# PSU_v1_0.net
KiCad netlist of a schematic drawn in EAGLE
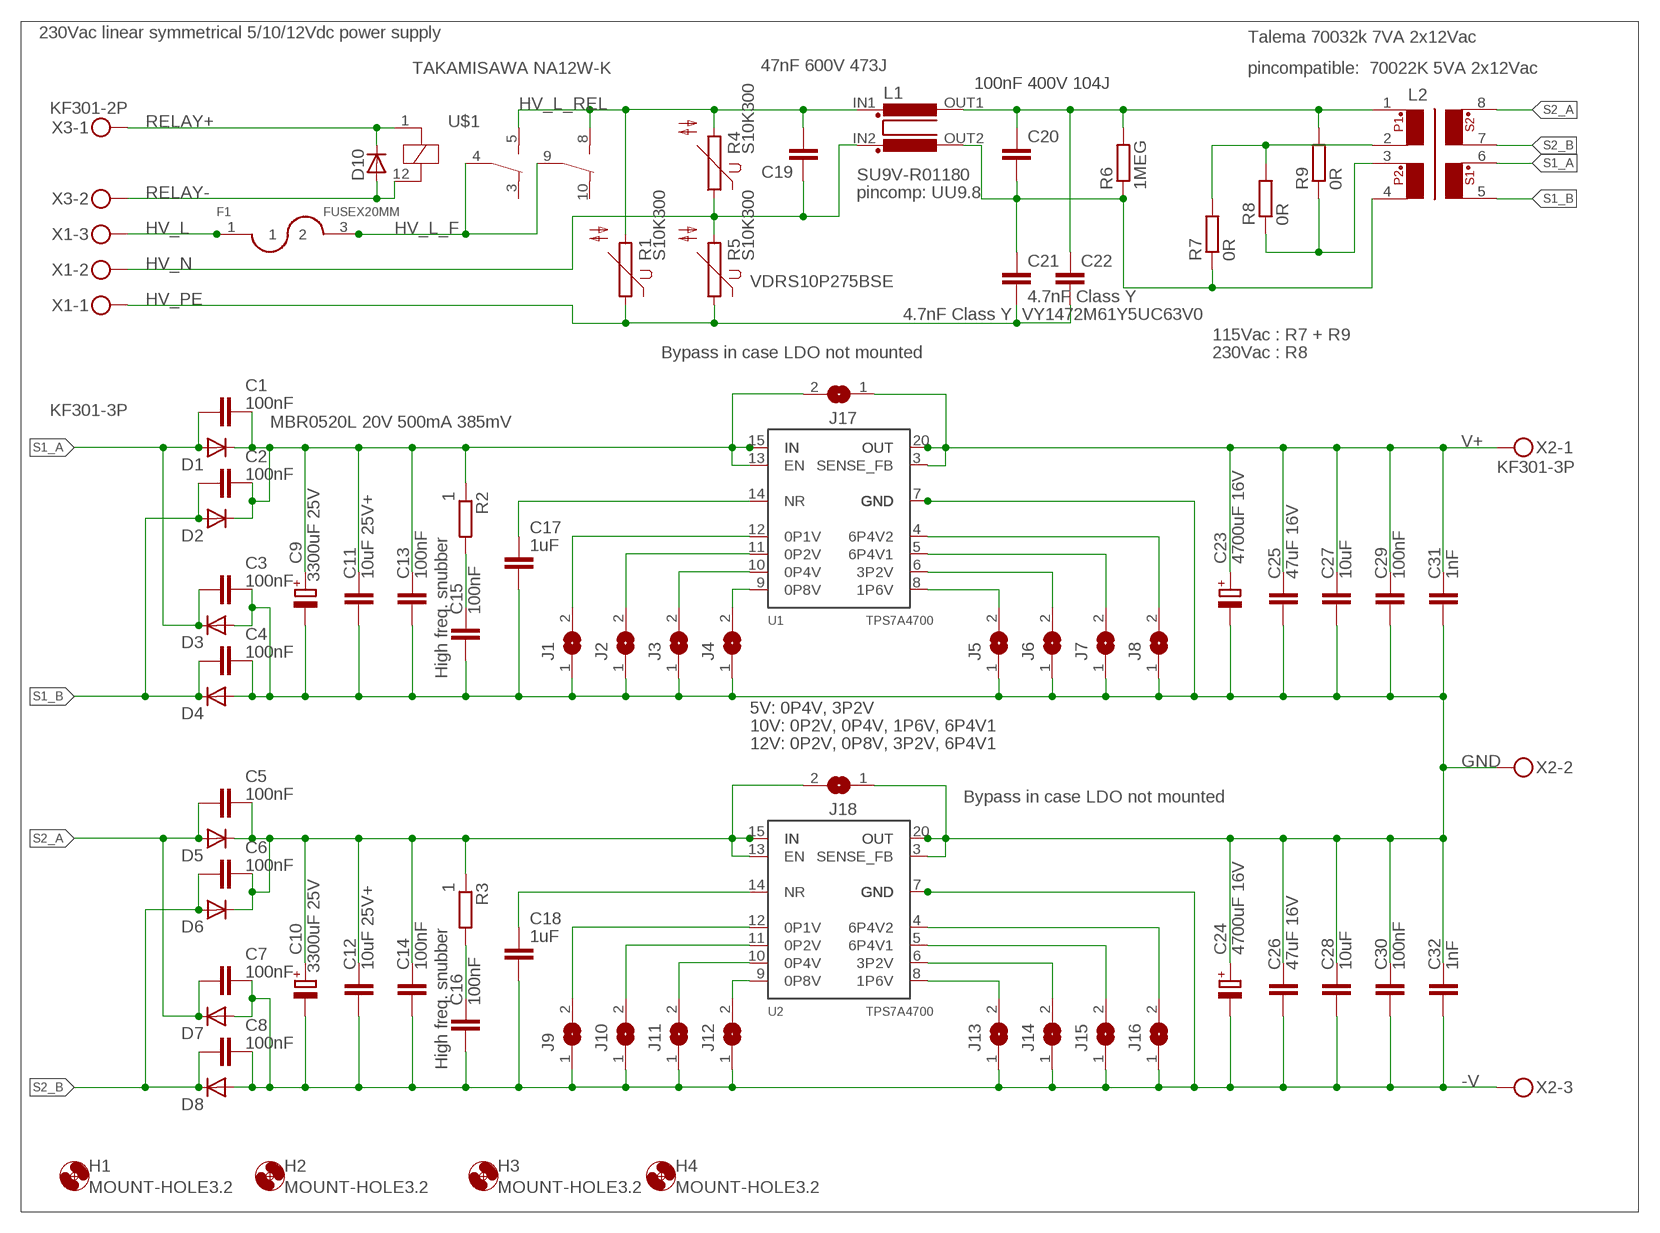
[diagram p0: schematic, sheet 1]

(export (version "E")
  (design (tool "Eeschema 10.0.6"))
  (components
    (comp (ref "C1")
      (value "100nF")
      (footprint "eagle-import:C0603")
      (libsource (lib "eagle-import") (part "C-EUC0603"))
    )
    (comp (ref "C2")
      (value "100nF")
      (footprint "eagle-import:C0603")
      (libsource (lib "eagle-import") (part "C-EUC0603"))
    )
    (comp (ref "C3")
      (value "100nF")
      (footprint "eagle-import:C0603")
      (libsource (lib "eagle-import") (part "C-EUC0603"))
    )
    (comp (ref "C4")
      (value "100nF")
      (footprint "eagle-import:C0603")
      (libsource (lib "eagle-import") (part "C-EUC0603"))
    )
    (comp (ref "C5")
      (value "100nF")
      (footprint "eagle-import:C0603")
      (libsource (lib "eagle-import") (part "C-EUC0603"))
    )
    (comp (ref "C6")
      (value "100nF")
      (footprint "eagle-import:C0603")
      (libsource (lib "eagle-import") (part "C-EUC0603"))
    )
    (comp (ref "C7")
      (value "100nF")
      (footprint "eagle-import:C0603")
      (libsource (lib "eagle-import") (part "C-EUC0603"))
    )
    (comp (ref "C8")
      (value "100nF")
      (footprint "eagle-import:C0603")
      (libsource (lib "eagle-import") (part "C-EUC0603"))
    )
    (comp (ref "C9")
      (value "3300uF 25V")
      (footprint "eagle-import:E7,5-16")
      (libsource (lib "eagle-import") (part "CPOL-EUE7.5-16"))
    )
    (comp (ref "C10")
      (value "3300uF 25V")
      (footprint "eagle-import:E7,5-16")
      (libsource (lib "eagle-import") (part "CPOL-EUE7.5-16"))
    )
    (comp (ref "C11")
      (value "10uF 25V+")
      (footprint "eagle-import:C1206")
      (libsource (lib "eagle-import") (part "C-EUC1206"))
    )
    (comp (ref "C12")
      (value "10uF 25V+")
      (footprint "eagle-import:C1206")
      (libsource (lib "eagle-import") (part "C-EUC1206"))
    )
    (comp (ref "C13")
      (value "100nF")
      (footprint "eagle-import:C0603")
      (libsource (lib "eagle-import") (part "C-EUC0603"))
    )
    (comp (ref "C14")
      (value "100nF")
      (footprint "eagle-import:C0603")
      (libsource (lib "eagle-import") (part "C-EUC0603"))
    )
    (comp (ref "C15")
      (value "100nF")
      (footprint "eagle-import:C0603")
      (libsource (lib "eagle-import") (part "C-EUC0603"))
    )
    (comp (ref "C16")
      (value "100nF")
      (footprint "eagle-import:C0603")
      (libsource (lib "eagle-import") (part "C-EUC0603"))
    )
    (comp (ref "C17")
      (value "1uF")
      (footprint "eagle-import:C0603")
      (libsource (lib "eagle-import") (part "C-EUC0603"))
    )
    (comp (ref "C18")
      (value "1uF")
      (footprint "eagle-import:C0603")
      (libsource (lib "eagle-import") (part "C-EUC0603"))
    )
    (comp (ref "C19")
      (value "47nF 600V 473J")
      (footprint "eagle-import:C102-054X133")
      (libsource (lib "eagle-import") (part "C-EU102-054X133"))
    )
    (comp (ref "C20")
      (value "100nF 400V 104J")
      (footprint "eagle-import:C102-064X133")
      (libsource (lib "eagle-import") (part "C-EU102-064X133"))
    )
    (comp (ref "C21")
      (value "4.7nF Class Y VY1472M61Y5UC63V0")
      (footprint "eagle-import:C102-043X133")
      (libsource (lib "eagle-import") (part "C-EU102-043X133"))
    )
    (comp (ref "C22")
      (value "4.7nF Class Y")
      (footprint "eagle-import:C102-043X133")
      (libsource (lib "eagle-import") (part "C-EU102-043X133"))
    )
    (comp (ref "C23")
      (value "4700uF 16V")
      (footprint "eagle-import:E7,5-16")
      (libsource (lib "eagle-import") (part "CPOL-EUE7.5-16"))
    )
    (comp (ref "C24")
      (value "4700uF 16V")
      (footprint "eagle-import:E7,5-16")
      (libsource (lib "eagle-import") (part "CPOL-EUE7.5-16"))
    )
    (comp (ref "C25")
      (value "47uF 16V")
      (footprint "eagle-import:C1210")
      (libsource (lib "eagle-import") (part "C-EUC1210"))
    )
    (comp (ref "C26")
      (value "47uF 16V")
      (footprint "eagle-import:C1210")
      (libsource (lib "eagle-import") (part "C-EUC1210"))
    )
    (comp (ref "C27")
      (value "10uF")
      (footprint "eagle-import:C1206")
      (libsource (lib "eagle-import") (part "C-EUC1206"))
    )
    (comp (ref "C28")
      (value "10uF")
      (footprint "eagle-import:C1206")
      (libsource (lib "eagle-import") (part "C-EUC1206"))
    )
    (comp (ref "C29")
      (value "100nF")
      (footprint "eagle-import:C0603")
      (libsource (lib "eagle-import") (part "C-EUC0603"))
    )
    (comp (ref "C30")
      (value "100nF")
      (footprint "eagle-import:C0603")
      (libsource (lib "eagle-import") (part "C-EUC0603"))
    )
    (comp (ref "C31")
      (value "1nF")
      (footprint "eagle-import:C0603")
      (libsource (lib "eagle-import") (part "C-EUC0603"))
    )
    (comp (ref "C32")
      (value "1nF")
      (footprint "eagle-import:C0603")
      (libsource (lib "eagle-import") (part "C-EUC0603"))
    )
    (comp (ref "D1")
      (value "MBR0520L 20V 500mA 385mV")
      (footprint "eagle-import:SOD123")
      (libsource (lib "eagle-import") (part "D-SOD123"))
    )
    (comp (ref "D2")
      (value "D-SOD123")
      (footprint "eagle-import:SOD123")
      (libsource (lib "eagle-import") (part "D-SOD123"))
    )
    (comp (ref "D3")
      (value "D-SOD123")
      (footprint "eagle-import:SOD123")
      (libsource (lib "eagle-import") (part "D-SOD123"))
    )
    (comp (ref "D4")
      (value "D-SOD123")
      (footprint "eagle-import:SOD123")
      (libsource (lib "eagle-import") (part "D-SOD123"))
    )
    (comp (ref "D5")
      (value "D-SOD123")
      (footprint "eagle-import:SOD123")
      (libsource (lib "eagle-import") (part "D-SOD123"))
    )
    (comp (ref "D6")
      (value "D-SOD123")
      (footprint "eagle-import:SOD123")
      (libsource (lib "eagle-import") (part "D-SOD123"))
    )
    (comp (ref "D7")
      (value "D-SOD123")
      (footprint "eagle-import:SOD123")
      (libsource (lib "eagle-import") (part "D-SOD123"))
    )
    (comp (ref "D8")
      (value "D-SOD123")
      (footprint "eagle-import:SOD123")
      (libsource (lib "eagle-import") (part "D-SOD123"))
    )
    (comp (ref "D10")
      (value "ES1A 50V 1A 25ns")
      (footprint "eagle-import:SOD123")
      (libsource (lib "eagle-import") (part "D-SOD123"))
    )
    (comp (ref "F1")
      (value "FUSEX20MM")
      (footprint "eagle-import:FUSE_5MM")
      (libsource (lib "eagle-import") (part "FUSEX20MM"))
    )
    (comp (ref "H1")
      (value "MOUNT-HOLE3.2")
      (footprint "eagle-import:3,2")
      (libsource (lib "eagle-import") (part "MOUNT-HOLE3.2"))
    )
    (comp (ref "H2")
      (value "MOUNT-HOLE3.2")
      (footprint "eagle-import:3,2")
      (libsource (lib "eagle-import") (part "MOUNT-HOLE3.2"))
    )
    (comp (ref "H3")
      (value "MOUNT-HOLE3.2")
      (footprint "eagle-import:3,2")
      (libsource (lib "eagle-import") (part "MOUNT-HOLE3.2"))
    )
    (comp (ref "H4")
      (value "MOUNT-HOLE3.2")
      (footprint "eagle-import:3,2")
      (libsource (lib "eagle-import") (part "MOUNT-HOLE3.2"))
    )
    (comp (ref "J1") (value "SJ") (footprint "eagle-import:SJ") (libsource (lib "eagle-import") (part "SJ")))
    (comp (ref "J2") (value "SJ") (footprint "eagle-import:SJ") (libsource (lib "eagle-import") (part "SJ")))
    (comp (ref "J3") (value "SJ") (footprint "eagle-import:SJ") (libsource (lib "eagle-import") (part "SJ")))
    (comp (ref "J4") (value "SJ") (footprint "eagle-import:SJ") (libsource (lib "eagle-import") (part "SJ")))
    (comp (ref "J5") (value "SJ") (footprint "eagle-import:SJ") (libsource (lib "eagle-import") (part "SJ")))
    (comp (ref "J6") (value "SJ") (footprint "eagle-import:SJ") (libsource (lib "eagle-import") (part "SJ")))
    (comp (ref "J7") (value "SJ") (footprint "eagle-import:SJ") (libsource (lib "eagle-import") (part "SJ")))
    (comp (ref "J8") (value "SJ") (footprint "eagle-import:SJ") (libsource (lib "eagle-import") (part "SJ")))
    (comp (ref "J9") (value "SJ") (footprint "eagle-import:SJ") (libsource (lib "eagle-import") (part "SJ")))
    (comp (ref "J10") (value "SJ") (footprint "eagle-import:SJ") (libsource (lib "eagle-import") (part "SJ")))
    (comp (ref "J11") (value "SJ") (footprint "eagle-import:SJ") (libsource (lib "eagle-import") (part "SJ")))
    (comp (ref "J12") (value "SJ") (footprint "eagle-import:SJ") (libsource (lib "eagle-import") (part "SJ")))
    (comp (ref "J13") (value "SJ") (footprint "eagle-import:SJ") (libsource (lib "eagle-import") (part "SJ")))
    (comp (ref "J14") (value "SJ") (footprint "eagle-import:SJ") (libsource (lib "eagle-import") (part "SJ")))
    (comp (ref "J15") (value "SJ") (footprint "eagle-import:SJ") (libsource (lib "eagle-import") (part "SJ")))
    (comp (ref "J16") (value "SJ") (footprint "eagle-import:SJ") (libsource (lib "eagle-import") (part "SJ")))
    (comp (ref "J17") (value "SJ") (footprint "eagle-import:SJ") (libsource (lib "eagle-import") (part "SJ")))
    (comp (ref "J18") (value "SJ") (footprint "eagle-import:SJ") (libsource (lib "eagle-import") (part "SJ")))
    (comp (ref "L1")
      (value "SU9V-R01180")
      (footprint "eagle-import:SU9V-R01180")
      (libsource (lib "eagle-import") (part "SU9V-R01180"))
    )
    (comp (ref "L2")
      (value "Talema 70032k 7VA 2x12Vac")
      (footprint "eagle-import:TALEMA_70000")
      (libsource (lib "eagle-import") (part "TALEMA_70000"))
    )
    (comp (ref "R1")
      (value "S10K300")
      (footprint "eagle-import:S10K300")
      (libsource (lib "eagle-import") (part "S10K300"))
    )
    (comp (ref "R2")
      (value "1")
      (footprint "eagle-import:R0603")
      (libsource (lib "eagle-import") (part "R-EU_R0603"))
    )
    (comp (ref "R3")
      (value "1")
      (footprint "eagle-import:R0603")
      (libsource (lib "eagle-import") (part "R-EU_R0603"))
    )
    (comp (ref "R4")
      (value "S10K300")
      (footprint "eagle-import:S10K300")
      (libsource (lib "eagle-import") (part "S10K300"))
    )
    (comp (ref "R5")
      (value "S10K300")
      (footprint "eagle-import:S10K300")
      (libsource (lib "eagle-import") (part "S10K300"))
    )
    (comp (ref "R6")
      (value "1MEG")
      (footprint "eagle-import:0309_12")
      (libsource (lib "eagle-import") (part "R-EU_0309/12"))
    )
    (comp (ref "R7")
      (value "0R")
      (footprint "eagle-import:0204_7")
      (libsource (lib "eagle-import") (part "R-EU_0204/7"))
    )
    (comp (ref "R8")
      (value "0R")
      (footprint "eagle-import:0204_7")
      (libsource (lib "eagle-import") (part "R-EU_0204/7"))
    )
    (comp (ref "R9")
      (value "0R")
      (footprint "eagle-import:0204_7")
      (libsource (lib "eagle-import") (part "R-EU_0204/7"))
    )
    (comp (ref "U$1")
      (value "TAKAMISAWA NA12W-K")
      (footprint "eagle-import:NA_RELAY")
      (libsource (lib "eagle-import") (part "NA_RELAY"))
    )
    (comp (ref "U1")
      (value "TPS7A4700")
      (footprint "eagle-import:VQFN20")
      (libsource (lib "eagle-import") (part "TPS7A4700"))
    )
    (comp (ref "U2")
      (value "TPS7A4700")
      (footprint "eagle-import:VQFN20")
      (libsource (lib "eagle-import") (part "TPS7A4700"))
    )
    (comp (ref "X1")
      (value "KF301-3P")
      (footprint "eagle-import:KF301-3P")
      (libsource (lib "eagle-import") (part "KF301-3P"))
    )
    (comp (ref "X2")
      (value "KF301-3P")
      (footprint "eagle-import:KF301-3P")
      (libsource (lib "eagle-import") (part "KF301-3P"))
    )
    (comp (ref "X3")
      (value "KF301-2P")
      (footprint "eagle-import:KF301-2P")
      (libsource (lib "eagle-import") (part "KF301-2P"))
    )
  )
  (nets
    (net (code "1") (name "/-V") (class "Default")
      (node (ref "C10") (pin "-") (pinfunction "-_-") (pintype "passive"))
      (node (ref "C12") (pin "1") (pinfunction "1_1") (pintype "passive"))
      (node (ref "C14") (pin "1") (pinfunction "1_1") (pintype "passive"))
      (node (ref "C16") (pin "1") (pinfunction "1_1") (pintype "passive"))
      (node (ref "C18") (pin "1") (pinfunction "1_1") (pintype "passive"))
      (node (ref "C24") (pin "-") (pinfunction "-_-") (pintype "passive"))
      (node (ref "C26") (pin "2") (pinfunction "2_2") (pintype "passive"))
      (node (ref "C28") (pin "1") (pinfunction "1_1") (pintype "passive"))
      (node (ref "C30") (pin "1") (pinfunction "1_1") (pintype "passive"))
      (node (ref "C32") (pin "1") (pinfunction "1_1") (pintype "passive"))
      (node (ref "C7") (pin "2") (pinfunction "2_2") (pintype "passive"))
      (node (ref "C8") (pin "2") (pinfunction "2_2") (pintype "passive"))
      (node (ref "D7") (pin "2") (pinfunction "A_2") (pintype "passive"))
      (node (ref "D8") (pin "2") (pinfunction "A_2") (pintype "passive"))
      (node (ref "J10") (pin "1") (pinfunction "1_1") (pintype "passive"))
      (node (ref "J11") (pin "1") (pinfunction "1_1") (pintype "passive"))
      (node (ref "J12") (pin "1") (pinfunction "1_1") (pintype "passive"))
      (node (ref "J13") (pin "1") (pinfunction "1_1") (pintype "passive"))
      (node (ref "J14") (pin "1") (pinfunction "1_1") (pintype "passive"))
      (node (ref "J15") (pin "1") (pinfunction "1_1") (pintype "passive"))
      (node (ref "J16") (pin "1") (pinfunction "1_1") (pintype "passive"))
      (node (ref "J9") (pin "1") (pinfunction "1_1") (pintype "passive"))
      (node (ref "U2") (pin "17") (pinfunction "GND_17") (pintype "bidirectional"))
      (node (ref "U2") (pin "18") (pinfunction "GND_18") (pintype "bidirectional"))
      (node (ref "U2") (pin "19") (pinfunction "GND_19") (pintype "bidirectional"))
      (node (ref "U2") (pin "21") (pinfunction "GND_21") (pintype "bidirectional"))
      (node (ref "U2") (pin "7") (pinfunction "GND_7") (pintype "bidirectional"))
      (node (ref "X2") (pin "3") (pinfunction "KL_3") (pintype "passive"))
    )
    (net (code "2") (name "/GND") (class "Default")
      (node (ref "C11") (pin "1") (pinfunction "1_1") (pintype "passive"))
      (node (ref "C13") (pin "1") (pinfunction "1_1") (pintype "passive"))
      (node (ref "C15") (pin "1") (pinfunction "1_1") (pintype "passive"))
      (node (ref "C17") (pin "1") (pinfunction "1_1") (pintype "passive"))
      (node (ref "C23") (pin "-") (pinfunction "-_-") (pintype "passive"))
      (node (ref "C24") (pin "+") (pinfunction "+_+") (pintype "passive"))
      (node (ref "C25") (pin "2") (pinfunction "2_2") (pintype "passive"))
      (node (ref "C26") (pin "1") (pinfunction "1_1") (pintype "passive"))
      (node (ref "C27") (pin "1") (pinfunction "1_1") (pintype "passive"))
      (node (ref "C28") (pin "2") (pinfunction "2_2") (pintype "passive"))
      (node (ref "C29") (pin "1") (pinfunction "1_1") (pintype "passive"))
      (node (ref "C3") (pin "2") (pinfunction "2_2") (pintype "passive"))
      (node (ref "C30") (pin "2") (pinfunction "2_2") (pintype "passive"))
      (node (ref "C31") (pin "1") (pinfunction "1_1") (pintype "passive"))
      (node (ref "C32") (pin "2") (pinfunction "2_2") (pintype "passive"))
      (node (ref "C4") (pin "2") (pinfunction "2_2") (pintype "passive"))
      (node (ref "C9") (pin "-") (pinfunction "-_-") (pintype "passive"))
      (node (ref "D3") (pin "2") (pinfunction "A_2") (pintype "passive"))
      (node (ref "D4") (pin "2") (pinfunction "A_2") (pintype "passive"))
      (node (ref "J1") (pin "1") (pinfunction "1_1") (pintype "passive"))
      (node (ref "J18") (pin "1") (pinfunction "1_1") (pintype "passive"))
      (node (ref "J2") (pin "1") (pinfunction "1_1") (pintype "passive"))
      (node (ref "J3") (pin "1") (pinfunction "1_1") (pintype "passive"))
      (node (ref "J4") (pin "1") (pinfunction "1_1") (pintype "passive"))
      (node (ref "J5") (pin "1") (pinfunction "1_1") (pintype "passive"))
      (node (ref "J6") (pin "1") (pinfunction "1_1") (pintype "passive"))
      (node (ref "J7") (pin "1") (pinfunction "1_1") (pintype "passive"))
      (node (ref "J8") (pin "1") (pinfunction "1_1") (pintype "passive"))
      (node (ref "U1") (pin "17") (pinfunction "GND_17") (pintype "bidirectional"))
      (node (ref "U1") (pin "18") (pinfunction "GND_18") (pintype "bidirectional"))
      (node (ref "U1") (pin "19") (pinfunction "GND_19") (pintype "bidirectional"))
      (node (ref "U1") (pin "21") (pinfunction "GND_21") (pintype "bidirectional"))
      (node (ref "U1") (pin "7") (pinfunction "GND_7") (pintype "bidirectional"))
      (node (ref "U2") (pin "1") (pinfunction "OUT_1") (pintype "bidirectional"))
      (node (ref "U2") (pin "20") (pinfunction "OUT_20") (pintype "bidirectional"))
      (node (ref "U2") (pin "3") (pinfunction "SENSE_FB_3") (pintype "bidirectional"))
      (node (ref "X2") (pin "2") (pinfunction "KL_2") (pintype "passive"))
    )
    (net (code "3") (name "/HV_L") (class "Default")
      (node (ref "F1") (pin "1") (pinfunction "1_1") (pintype "bidirectional"))
      (node (ref "F1") (pin "2") (pinfunction "3_2") (pintype "bidirectional"))
      (node (ref "X1") (pin "3") (pinfunction "KL_3") (pintype "passive"))
    )
    (net (code "4") (name "/HV_L_F") (class "Default")
      (node (ref "F1") (pin "3") (pinfunction "2_3") (pintype "bidirectional"))
      (node (ref "F1") (pin "4") (pinfunction "4_4") (pintype "bidirectional"))
      (node (ref "U$1") (pin "4") (pinfunction "A_4") (pintype "passive"))
      (node (ref "U$1") (pin "9") (pinfunction "B_9") (pintype "passive"))
    )
    (net (code "5") (name "/HV_L_REL") (class "Default")
      (node (ref "C19") (pin "1") (pinfunction "1_1") (pintype "passive"))
      (node (ref "L1") (pin "IN1") (pinfunction "IN1_IN1") (pintype "passive"))
      (node (ref "R1") (pin "2") (pinfunction "2_2") (pintype "passive"))
      (node (ref "R4") (pin "2") (pinfunction "2_2") (pintype "passive"))
      (node (ref "U$1") (pin "5") (pinfunction "A_NO_5") (pintype "passive"))
      (node (ref "U$1") (pin "8") (pinfunction "B_NO_8") (pintype "passive"))
    )
    (net (code "6") (name "/HV_N") (class "Default")
      (node (ref "C19") (pin "2") (pinfunction "2_2") (pintype "passive"))
      (node (ref "L1") (pin "IN2") (pinfunction "IN2_IN2") (pintype "passive"))
      (node (ref "R4") (pin "1") (pinfunction "1_1") (pintype "passive"))
      (node (ref "R5") (pin "2") (pinfunction "2_2") (pintype "passive"))
      (node (ref "X1") (pin "2") (pinfunction "KL_2") (pintype "passive"))
    )
    (net (code "7") (name "/HV_PE") (class "Default")
      (node (ref "C21") (pin "2") (pinfunction "2_2") (pintype "passive"))
      (node (ref "C22") (pin "2") (pinfunction "2_2") (pintype "passive"))
      (node (ref "R1") (pin "1") (pinfunction "1_1") (pintype "passive"))
      (node (ref "R5") (pin "1") (pinfunction "1_1") (pintype "passive"))
      (node (ref "X1") (pin "1") (pinfunction "KL_1") (pintype "passive"))
    )
    (net (code "8") (name "/RELAY+") (class "Default")
      (node (ref "D10") (pin "1") (pinfunction "C_1") (pintype "passive"))
      (node (ref "U$1") (pin "1") (pinfunction "C+_1") (pintype "passive"))
      (node (ref "X3") (pin "2") (pinfunction "KL_2") (pintype "passive"))
    )
    (net (code "9") (name "/RELAY-") (class "Default")
      (node (ref "D10") (pin "2") (pinfunction "A_2") (pintype "passive"))
      (node (ref "U$1") (pin "12") (pinfunction "C-_12") (pintype "passive"))
      (node (ref "X3") (pin "3") (pinfunction "KL_3") (pintype "passive"))
    )
    (net (code "10") (name "/V+") (class "Default")
      (node (ref "C23") (pin "+") (pinfunction "+_+") (pintype "passive"))
      (node (ref "C25") (pin "1") (pinfunction "1_1") (pintype "passive"))
      (node (ref "C27") (pin "2") (pinfunction "2_2") (pintype "passive"))
      (node (ref "C29") (pin "2") (pinfunction "2_2") (pintype "passive"))
      (node (ref "C31") (pin "2") (pinfunction "2_2") (pintype "passive"))
      (node (ref "J17") (pin "1") (pinfunction "1_1") (pintype "passive"))
      (node (ref "U1") (pin "1") (pinfunction "OUT_1") (pintype "bidirectional"))
      (node (ref "U1") (pin "20") (pinfunction "OUT_20") (pintype "bidirectional"))
      (node (ref "U1") (pin "3") (pinfunction "SENSE_FB_3") (pintype "bidirectional"))
      (node (ref "X2") (pin "1") (pinfunction "KL_1") (pintype "passive"))
    )
    (net (code "11") (name "Net-(C15-Pad2)") (class "Default")
      (node (ref "C15") (pin "2") (pinfunction "2_2") (pintype "passive"))
      (node (ref "R2") (pin "2") (pinfunction "2_2") (pintype "passive"))
    )
    (net (code "12") (name "Net-(C16-Pad2)") (class "Default")
      (node (ref "C16") (pin "2") (pinfunction "2_2") (pintype "passive"))
      (node (ref "R3") (pin "2") (pinfunction "2_2") (pintype "passive"))
    )
    (net (code "13") (name "Net-(C20-Pad1)") (class "Default")
      (node (ref "C20") (pin "1") (pinfunction "1_1") (pintype "passive"))
      (node (ref "C22") (pin "1") (pinfunction "1_1") (pintype "passive"))
      (node (ref "L1") (pin "OUT1") (pinfunction "OUT1_OUT1") (pintype "passive"))
      (node (ref "L2") (pin "1") (pinfunction "1_1") (pintype "passive"))
      (node (ref "R6") (pin "2") (pinfunction "2_2") (pintype "passive"))
      (node (ref "R9") (pin "2") (pinfunction "2_2") (pintype "passive"))
    )
    (net (code "14") (name "Net-(C20-Pad2)") (class "Default")
      (node (ref "C20") (pin "2") (pinfunction "2_2") (pintype "passive"))
      (node (ref "C21") (pin "1") (pinfunction "1_1") (pintype "passive"))
      (node (ref "L1") (pin "OUT2") (pinfunction "OUT2_OUT2") (pintype "passive"))
      (node (ref "L2") (pin "4") (pinfunction "4_4") (pintype "passive"))
      (node (ref "R6") (pin "1") (pinfunction "1_1") (pintype "passive"))
      (node (ref "R7") (pin "1") (pinfunction "1_1") (pintype "passive"))
    )
    (net (code "15") (name "Net-(D1-C)") (class "Default")
      (node (ref "C1") (pin "2") (pinfunction "2_2") (pintype "passive"))
      (node (ref "C11") (pin "2") (pinfunction "2_2") (pintype "passive"))
      (node (ref "C13") (pin "2") (pinfunction "2_2") (pintype "passive"))
      (node (ref "C2") (pin "2") (pinfunction "2_2") (pintype "passive"))
      (node (ref "C9") (pin "+") (pinfunction "+_+") (pintype "passive"))
      (node (ref "D1") (pin "1") (pinfunction "C_1") (pintype "passive"))
      (node (ref "D2") (pin "1") (pinfunction "C_1") (pintype "passive"))
      (node (ref "J17") (pin "2") (pinfunction "2_2") (pintype "passive"))
      (node (ref "R2") (pin "1") (pinfunction "1_1") (pintype "passive"))
      (node (ref "U1") (pin "13") (pinfunction "EN_13") (pintype "bidirectional"))
      (node (ref "U1") (pin "15") (pinfunction "IN_15") (pintype "bidirectional"))
      (node (ref "U1") (pin "16") (pinfunction "IN_16") (pintype "bidirectional"))
    )
    (net (code "16") (name "Net-(D5-C)") (class "Default")
      (node (ref "C10") (pin "+") (pinfunction "+_+") (pintype "passive"))
      (node (ref "C12") (pin "2") (pinfunction "2_2") (pintype "passive"))
      (node (ref "C14") (pin "2") (pinfunction "2_2") (pintype "passive"))
      (node (ref "C5") (pin "2") (pinfunction "2_2") (pintype "passive"))
      (node (ref "C6") (pin "2") (pinfunction "2_2") (pintype "passive"))
      (node (ref "D5") (pin "1") (pinfunction "C_1") (pintype "passive"))
      (node (ref "D6") (pin "1") (pinfunction "C_1") (pintype "passive"))
      (node (ref "J18") (pin "2") (pinfunction "2_2") (pintype "passive"))
      (node (ref "R3") (pin "1") (pinfunction "1_1") (pintype "passive"))
      (node (ref "U2") (pin "13") (pinfunction "EN_13") (pintype "bidirectional"))
      (node (ref "U2") (pin "15") (pinfunction "IN_15") (pintype "bidirectional"))
      (node (ref "U2") (pin "16") (pinfunction "IN_16") (pintype "bidirectional"))
    )
    (net (code "17") (name "Net-(L2-Pad2)") (class "Default")
      (node (ref "L2") (pin "2") (pinfunction "2_2") (pintype "passive"))
      (node (ref "R7") (pin "2") (pinfunction "2_2") (pintype "passive"))
      (node (ref "R8") (pin "2") (pinfunction "2_2") (pintype "passive"))
    )
    (net (code "18") (name "Net-(L2-Pad3)") (class "Default")
      (node (ref "L2") (pin "3") (pinfunction "3_3") (pintype "passive"))
      (node (ref "R8") (pin "1") (pinfunction "1_1") (pintype "passive"))
      (node (ref "R9") (pin "1") (pinfunction "1_1") (pintype "passive"))
    )
    (net (code "19") (name "Net-(U1-0P1V)") (class "Default")
      (node (ref "J1") (pin "2") (pinfunction "2_2") (pintype "passive"))
      (node (ref "U1") (pin "12") (pinfunction "0P1V_12") (pintype "bidirectional"))
    )
    (net (code "20") (name "Net-(U1-0P2V)") (class "Default")
      (node (ref "J2") (pin "2") (pinfunction "2_2") (pintype "passive"))
      (node (ref "U1") (pin "11") (pinfunction "0P2V_11") (pintype "bidirectional"))
    )
    (net (code "21") (name "Net-(U1-0P4V)") (class "Default")
      (node (ref "J3") (pin "2") (pinfunction "2_2") (pintype "passive"))
      (node (ref "U1") (pin "10") (pinfunction "0P4V_10") (pintype "bidirectional"))
    )
    (net (code "22") (name "Net-(U1-0P8V)") (class "Default")
      (node (ref "J4") (pin "2") (pinfunction "2_2") (pintype "passive"))
      (node (ref "U1") (pin "9") (pinfunction "0P8V_9") (pintype "bidirectional"))
    )
    (net (code "23") (name "Net-(U1-1P6V)") (class "Default")
      (node (ref "J5") (pin "2") (pinfunction "2_2") (pintype "passive"))
      (node (ref "U1") (pin "8") (pinfunction "1P6V_8") (pintype "bidirectional"))
    )
    (net (code "24") (name "Net-(U1-3P2V)") (class "Default")
      (node (ref "J6") (pin "2") (pinfunction "2_2") (pintype "passive"))
      (node (ref "U1") (pin "6") (pinfunction "3P2V_6") (pintype "bidirectional"))
    )
    (net (code "25") (name "Net-(U1-6P4V1)") (class "Default")
      (node (ref "J7") (pin "2") (pinfunction "2_2") (pintype "passive"))
      (node (ref "U1") (pin "5") (pinfunction "6P4V1_5") (pintype "bidirectional"))
    )
    (net (code "26") (name "Net-(U1-6P4V2)") (class "Default")
      (node (ref "J8") (pin "2") (pinfunction "2_2") (pintype "passive"))
      (node (ref "U1") (pin "4") (pinfunction "6P4V2_4") (pintype "bidirectional"))
    )
    (net (code "27") (name "Net-(U1-NR)") (class "Default")
      (node (ref "C17") (pin "2") (pinfunction "2_2") (pintype "passive"))
      (node (ref "U1") (pin "14") (pinfunction "NR_14") (pintype "bidirectional"))
    )
    (net (code "28") (name "Net-(U2-0P1V)") (class "Default")
      (node (ref "J9") (pin "2") (pinfunction "2_2") (pintype "passive"))
      (node (ref "U2") (pin "12") (pinfunction "0P1V_12") (pintype "bidirectional"))
    )
    (net (code "29") (name "Net-(U2-0P2V)") (class "Default")
      (node (ref "J10") (pin "2") (pinfunction "2_2") (pintype "passive"))
      (node (ref "U2") (pin "11") (pinfunction "0P2V_11") (pintype "bidirectional"))
    )
    (net (code "30") (name "Net-(U2-0P4V)") (class "Default")
      (node (ref "J11") (pin "2") (pinfunction "2_2") (pintype "passive"))
      (node (ref "U2") (pin "10") (pinfunction "0P4V_10") (pintype "bidirectional"))
    )
    (net (code "31") (name "Net-(U2-0P8V)") (class "Default")
      (node (ref "J12") (pin "2") (pinfunction "2_2") (pintype "passive"))
      (node (ref "U2") (pin "9") (pinfunction "0P8V_9") (pintype "bidirectional"))
    )
    (net (code "32") (name "Net-(U2-1P6V)") (class "Default")
      (node (ref "J13") (pin "2") (pinfunction "2_2") (pintype "passive"))
      (node (ref "U2") (pin "8") (pinfunction "1P6V_8") (pintype "bidirectional"))
    )
    (net (code "33") (name "Net-(U2-3P2V)") (class "Default")
      (node (ref "J14") (pin "2") (pinfunction "2_2") (pintype "passive"))
      (node (ref "U2") (pin "6") (pinfunction "3P2V_6") (pintype "bidirectional"))
    )
    (net (code "34") (name "Net-(U2-6P4V1)") (class "Default")
      (node (ref "J15") (pin "2") (pinfunction "2_2") (pintype "passive"))
      (node (ref "U2") (pin "5") (pinfunction "6P4V1_5") (pintype "bidirectional"))
    )
    (net (code "35") (name "Net-(U2-6P4V2)") (class "Default")
      (node (ref "J16") (pin "2") (pinfunction "2_2") (pintype "passive"))
      (node (ref "U2") (pin "4") (pinfunction "6P4V2_4") (pintype "bidirectional"))
    )
    (net (code "36") (name "Net-(U2-NR)") (class "Default")
      (node (ref "C18") (pin "2") (pinfunction "2_2") (pintype "passive"))
      (node (ref "U2") (pin "14") (pinfunction "NR_14") (pintype "bidirectional"))
    )
    (net (code "37") (name "S1_A") (class "Default")
      (node (ref "C1") (pin "1") (pinfunction "1_1") (pintype "passive"))
      (node (ref "C3") (pin "1") (pinfunction "1_1") (pintype "passive"))
      (node (ref "D1") (pin "2") (pinfunction "A_2") (pintype "passive"))
      (node (ref "D3") (pin "1") (pinfunction "C_1") (pintype "passive"))
      (node (ref "L2") (pin "6") (pinfunction "6_6") (pintype "passive"))
    )
    (net (code "38") (name "S1_B") (class "Default")
      (node (ref "C2") (pin "1") (pinfunction "1_1") (pintype "passive"))
      (node (ref "C4") (pin "1") (pinfunction "1_1") (pintype "passive"))
      (node (ref "D2") (pin "2") (pinfunction "A_2") (pintype "passive"))
      (node (ref "D4") (pin "1") (pinfunction "C_1") (pintype "passive"))
      (node (ref "L2") (pin "5") (pinfunction "5_5") (pintype "passive"))
    )
    (net (code "39") (name "S2_A") (class "Default")
      (node (ref "C5") (pin "1") (pinfunction "1_1") (pintype "passive"))
      (node (ref "C7") (pin "1") (pinfunction "1_1") (pintype "passive"))
      (node (ref "D5") (pin "2") (pinfunction "A_2") (pintype "passive"))
      (node (ref "D7") (pin "1") (pinfunction "C_1") (pintype "passive"))
      (node (ref "L2") (pin "8") (pinfunction "8_8") (pintype "passive"))
    )
    (net (code "40") (name "S2_B") (class "Default")
      (node (ref "C6") (pin "1") (pinfunction "1_1") (pintype "passive"))
      (node (ref "C8") (pin "1") (pinfunction "1_1") (pintype "passive"))
      (node (ref "D6") (pin "2") (pinfunction "A_2") (pintype "passive"))
      (node (ref "D8") (pin "1") (pinfunction "C_1") (pintype "passive"))
      (node (ref "L2") (pin "7") (pinfunction "7_7") (pintype "passive"))
    )
    (net (code "41") (name "unconnected-(U$1-A_NC-Pad3)") (class "Default")
      (node (ref "U$1") (pin "3") (pinfunction "A_NC_3") (pintype "passive"))
    )
    (net (code "42") (name "unconnected-(U$1-B_NC-Pad10)") (class "Default")
      (node (ref "U$1") (pin "10") (pinfunction "B_NC_10") (pintype "passive"))
    )
  )
)
